# natb_square_chip.net
KiCad netlist of a schematic drawn in EAGLE
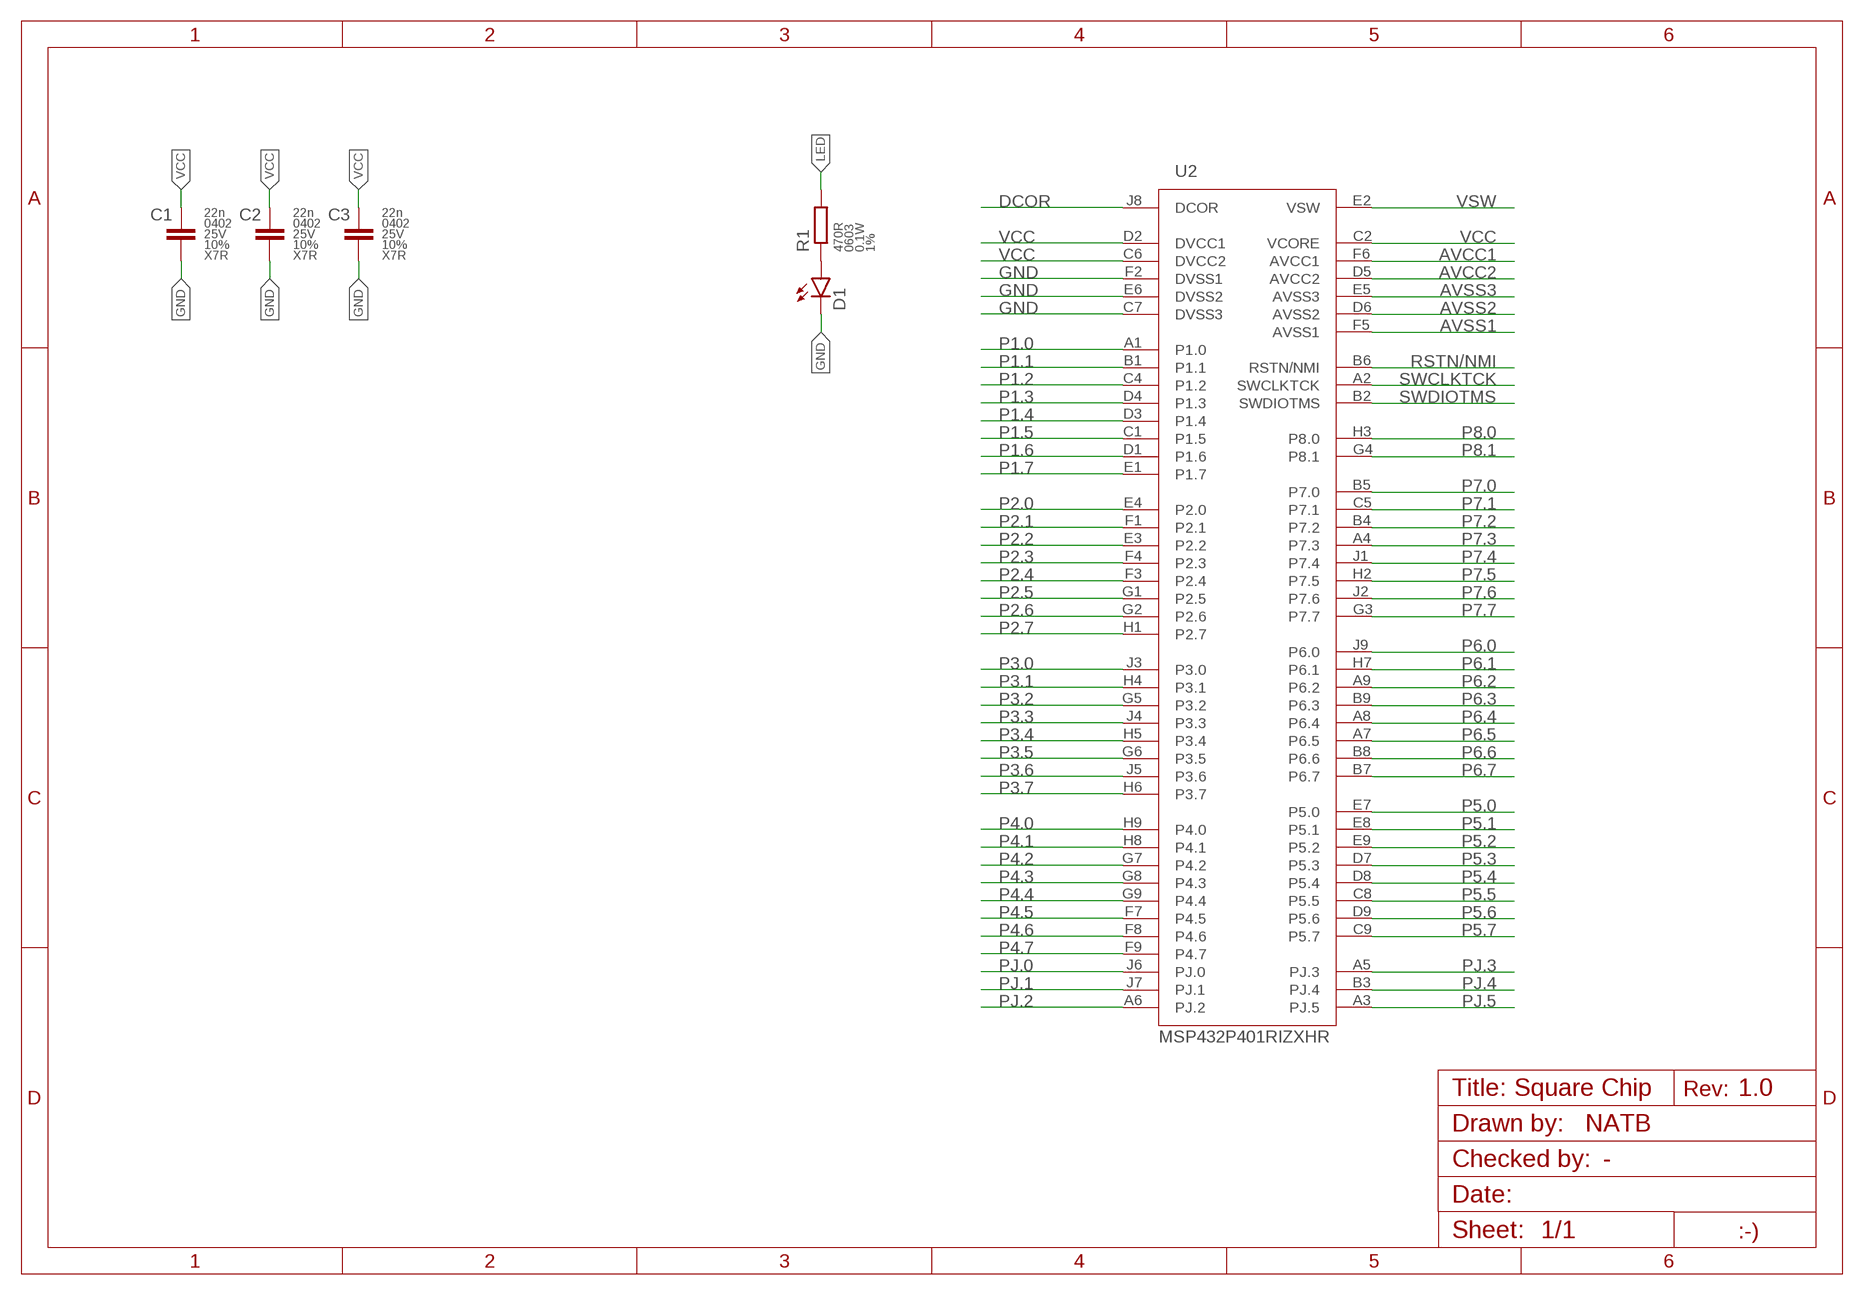
[diagram p0: schematic, sheet 1]

(export (version "E")
  (design (tool "Eeschema 10.0.6"))
  (components
    (comp (ref "C1")
      (value "22n")
      (footprint "eagle-import:C0402")
      (fields
        (field (name "PACKAGE-IN") "0402")
        (field (name "VOLTAGE") "25V")
        (field (name "TOLERANCE") "10%")
        (field (name "DIELECTRIC") "X7R")
        (field (name "MF") "Wurth Electronics")
        (field (name "MPN") "885012205052")
      )
      (libsource (lib "eagle-import") (part "22NF-0402-25V-10%"))
    )
    (comp (ref "C2")
      (value "22n")
      (footprint "eagle-import:C0402")
      (fields
        (field (name "PACKAGE-IN") "0402")
        (field (name "VOLTAGE") "25V")
        (field (name "TOLERANCE") "10%")
        (field (name "DIELECTRIC") "X7R")
        (field (name "MF") "Wurth Electronics")
        (field (name "MPN") "885012205052")
      )
      (libsource (lib "eagle-import") (part "22NF-0402-25V-10%"))
    )
    (comp (ref "C3")
      (value "22n")
      (footprint "eagle-import:C0402")
      (fields
        (field (name "PACKAGE-IN") "0402")
        (field (name "VOLTAGE") "25V")
        (field (name "TOLERANCE") "10%")
        (field (name "DIELECTRIC") "X7R")
        (field (name "MF") "Wurth Electronics")
        (field (name "MPN") "885012205052")
      )
      (libsource (lib "eagle-import") (part "22NF-0402-25V-10%"))
    )
    (comp (ref "D1")
      (value "LEDCHIP-LED0603")
      (footprint "eagle-import:CHIP-LED0603")
      (libsource (lib "eagle-import") (part "LEDCHIP-LED0603"))
    )
    (comp (ref "R1")
      (value "470R")
      (footprint "eagle-import:R0603")
      (fields
        (field (name "PACKAGE-IN") "0603")
        (field (name "POWER") "0.1W")
        (field (name "TOLERANCE") "1%")
        (field (name "MF") "Yageo")
        (field (name "MPN") "RC0603FR-07470RL")
        (field (name "VOLTAGE") "75V")
      )
      (libsource (lib "eagle-import") (part "470OHM-0603-1/10W-1%"))
    )
    (comp (ref "U2")
      (value "MSP432P401RIZXHR")
      (footprint "eagle-import:BGA80")
      (fields
        (field (name "DIGIKEY_PARTNO") "296-45566-6-ND")
        (field (name "MANUFACTURER") "Texas Instruments")
        (field (name "CREATED_BY") "PCBLayout.com")
      )
      (libsource (lib "eagle-import") (part "MSP432P401RIZXHR"))
    )
  )
  (nets
    (net (code "1") (name "/AVCC1") (class "Default")
      (node (ref "U2") (pin "F6") (pinfunction "AVCC1_F6") (pintype "power_in"))
    )
    (net (code "2") (name "/AVCC2") (class "Default")
      (node (ref "U2") (pin "D5") (pinfunction "AVCC2_D5") (pintype "power_in"))
    )
    (net (code "3") (name "/AVSS1") (class "Default")
      (node (ref "U2") (pin "F5") (pinfunction "AVSS1_F5") (pintype "power_in"))
    )
    (net (code "4") (name "/AVSS2") (class "Default")
      (node (ref "U2") (pin "D6") (pinfunction "AVSS2_D6") (pintype "power_in"))
    )
    (net (code "5") (name "/AVSS3") (class "Default")
      (node (ref "U2") (pin "E5") (pinfunction "AVSS3_E5") (pintype "power_in"))
    )
    (net (code "6") (name "/DCOR") (class "Default")
      (node (ref "U2") (pin "J8") (pinfunction "DCOR_J8") (pintype "power_in"))
    )
    (net (code "7") (name "/P1.0") (class "Default")
      (node (ref "U2") (pin "A1") (pinfunction "P1.0_A1") (pintype "bidirectional"))
    )
    (net (code "8") (name "/P1.1") (class "Default")
      (node (ref "U2") (pin "B1") (pinfunction "P1.1_B1") (pintype "bidirectional"))
    )
    (net (code "9") (name "/P1.2") (class "Default")
      (node (ref "U2") (pin "C4") (pinfunction "P1.2_C4") (pintype "bidirectional"))
    )
    (net (code "10") (name "/P1.3") (class "Default")
      (node (ref "U2") (pin "D4") (pinfunction "P1.3_D4") (pintype "bidirectional"))
    )
    (net (code "11") (name "/P1.4") (class "Default")
      (node (ref "U2") (pin "D3") (pinfunction "P1.4_D3") (pintype "bidirectional"))
    )
    (net (code "12") (name "/P1.5") (class "Default")
      (node (ref "U2") (pin "C1") (pinfunction "P1.5_C1") (pintype "bidirectional"))
    )
    (net (code "13") (name "/P1.6") (class "Default")
      (node (ref "U2") (pin "D1") (pinfunction "P1.6_D1") (pintype "bidirectional"))
    )
    (net (code "14") (name "/P1.7") (class "Default")
      (node (ref "U2") (pin "E1") (pinfunction "P1.7_E1") (pintype "bidirectional"))
    )
    (net (code "15") (name "/P2.0") (class "Default")
      (node (ref "U2") (pin "E4") (pinfunction "P2.0_E4") (pintype "bidirectional"))
    )
    (net (code "16") (name "/P2.1") (class "Default")
      (node (ref "U2") (pin "F1") (pinfunction "P2.1_F1") (pintype "bidirectional"))
    )
    (net (code "17") (name "/P2.2") (class "Default")
      (node (ref "U2") (pin "E3") (pinfunction "P2.2_E3") (pintype "bidirectional"))
    )
    (net (code "18") (name "/P2.3") (class "Default")
      (node (ref "U2") (pin "F4") (pinfunction "P2.3_F4") (pintype "bidirectional"))
    )
    (net (code "19") (name "/P2.4") (class "Default")
      (node (ref "U2") (pin "F3") (pinfunction "P2.4_F3") (pintype "bidirectional"))
    )
    (net (code "20") (name "/P2.5") (class "Default")
      (node (ref "U2") (pin "G1") (pinfunction "P2.5_G1") (pintype "bidirectional"))
    )
    (net (code "21") (name "/P2.6") (class "Default")
      (node (ref "U2") (pin "G2") (pinfunction "P2.6_G2") (pintype "bidirectional"))
    )
    (net (code "22") (name "/P2.7") (class "Default")
      (node (ref "U2") (pin "H1") (pinfunction "P2.7_H1") (pintype "bidirectional"))
    )
    (net (code "23") (name "/P3.0") (class "Default")
      (node (ref "U2") (pin "J3") (pinfunction "P3.0_J3") (pintype "bidirectional"))
    )
    (net (code "24") (name "/P3.1") (class "Default")
      (node (ref "U2") (pin "H4") (pinfunction "P3.1_H4") (pintype "bidirectional"))
    )
    (net (code "25") (name "/P3.2") (class "Default")
      (node (ref "U2") (pin "G5") (pinfunction "P3.2_G5") (pintype "bidirectional"))
    )
    (net (code "26") (name "/P3.3") (class "Default")
      (node (ref "U2") (pin "J4") (pinfunction "P3.3_J4") (pintype "bidirectional"))
    )
    (net (code "27") (name "/P3.4") (class "Default")
      (node (ref "U2") (pin "H5") (pinfunction "P3.4_H5") (pintype "bidirectional"))
    )
    (net (code "28") (name "/P3.5") (class "Default")
      (node (ref "U2") (pin "G6") (pinfunction "P3.5_G6") (pintype "bidirectional"))
    )
    (net (code "29") (name "/P3.6") (class "Default")
      (node (ref "U2") (pin "J5") (pinfunction "P3.6_J5") (pintype "bidirectional"))
    )
    (net (code "30") (name "/P3.7") (class "Default")
      (node (ref "U2") (pin "H6") (pinfunction "P3.7_H6") (pintype "bidirectional"))
    )
    (net (code "31") (name "/P4.0") (class "Default")
      (node (ref "U2") (pin "H9") (pinfunction "P4.0_H9") (pintype "bidirectional"))
    )
    (net (code "32") (name "/P4.1") (class "Default")
      (node (ref "U2") (pin "H8") (pinfunction "P4.1_H8") (pintype "bidirectional"))
    )
    (net (code "33") (name "/P4.2") (class "Default")
      (node (ref "U2") (pin "G7") (pinfunction "P4.2_G7") (pintype "bidirectional"))
    )
    (net (code "34") (name "/P4.3") (class "Default")
      (node (ref "U2") (pin "G8") (pinfunction "P4.3_G8") (pintype "bidirectional"))
    )
    (net (code "35") (name "/P4.4") (class "Default")
      (node (ref "U2") (pin "G9") (pinfunction "P4.4_G9") (pintype "bidirectional"))
    )
    (net (code "36") (name "/P4.5") (class "Default")
      (node (ref "U2") (pin "F7") (pinfunction "P4.5_F7") (pintype "bidirectional"))
    )
    (net (code "37") (name "/P4.6") (class "Default")
      (node (ref "U2") (pin "F8") (pinfunction "P4.6_F8") (pintype "bidirectional"))
    )
    (net (code "38") (name "/P4.7") (class "Default")
      (node (ref "U2") (pin "F9") (pinfunction "P4.7_F9") (pintype "bidirectional"))
    )
    (net (code "39") (name "/P5.0") (class "Default")
      (node (ref "U2") (pin "E7") (pinfunction "P5.0_E7") (pintype "bidirectional"))
    )
    (net (code "40") (name "/P5.1") (class "Default")
      (node (ref "U2") (pin "E8") (pinfunction "P5.1_E8") (pintype "bidirectional"))
    )
    (net (code "41") (name "/P5.2") (class "Default")
      (node (ref "U2") (pin "E9") (pinfunction "P5.2_E9") (pintype "bidirectional"))
    )
    (net (code "42") (name "/P5.3") (class "Default")
      (node (ref "U2") (pin "D7") (pinfunction "P5.3_D7") (pintype "bidirectional"))
    )
    (net (code "43") (name "/P5.4") (class "Default")
      (node (ref "U2") (pin "D8") (pinfunction "P5.4_D8") (pintype "bidirectional"))
    )
    (net (code "44") (name "/P5.5") (class "Default")
      (node (ref "U2") (pin "C8") (pinfunction "P5.5_C8") (pintype "bidirectional"))
    )
    (net (code "45") (name "/P5.6") (class "Default")
      (node (ref "U2") (pin "D9") (pinfunction "P5.6_D9") (pintype "bidirectional"))
    )
    (net (code "46") (name "/P5.7") (class "Default")
      (node (ref "U2") (pin "C9") (pinfunction "P5.7_C9") (pintype "bidirectional"))
    )
    (net (code "47") (name "/P6.0") (class "Default")
      (node (ref "U2") (pin "J9") (pinfunction "P6.0_J9") (pintype "bidirectional"))
    )
    (net (code "48") (name "/P6.1") (class "Default")
      (node (ref "U2") (pin "H7") (pinfunction "P6.1_H7") (pintype "bidirectional"))
    )
    (net (code "49") (name "/P6.2") (class "Default")
      (node (ref "U2") (pin "A9") (pinfunction "P6.2_A9") (pintype "bidirectional"))
    )
    (net (code "50") (name "/P6.3") (class "Default")
      (node (ref "U2") (pin "B9") (pinfunction "P6.3_B9") (pintype "bidirectional"))
    )
    (net (code "51") (name "/P6.4") (class "Default")
      (node (ref "U2") (pin "A8") (pinfunction "P6.4_A8") (pintype "bidirectional"))
    )
    (net (code "52") (name "/P6.5") (class "Default")
      (node (ref "U2") (pin "A7") (pinfunction "P6.5_A7") (pintype "bidirectional"))
    )
    (net (code "53") (name "/P6.6") (class "Default")
      (node (ref "U2") (pin "B8") (pinfunction "P6.6_B8") (pintype "bidirectional"))
    )
    (net (code "54") (name "/P6.7") (class "Default")
      (node (ref "U2") (pin "B7") (pinfunction "P6.7_B7") (pintype "bidirectional"))
    )
    (net (code "55") (name "/P7.0") (class "Default")
      (node (ref "U2") (pin "B5") (pinfunction "P7.0_B5") (pintype "bidirectional"))
    )
    (net (code "56") (name "/P7.1") (class "Default")
      (node (ref "U2") (pin "C5") (pinfunction "P7.1_C5") (pintype "bidirectional"))
    )
    (net (code "57") (name "/P7.2") (class "Default")
      (node (ref "U2") (pin "B4") (pinfunction "P7.2_B4") (pintype "bidirectional"))
    )
    (net (code "58") (name "/P7.3") (class "Default")
      (node (ref "U2") (pin "A4") (pinfunction "P7.3_A4") (pintype "bidirectional"))
    )
    (net (code "59") (name "/P7.4") (class "Default")
      (node (ref "U2") (pin "J1") (pinfunction "P7.4_J1") (pintype "bidirectional"))
    )
    (net (code "60") (name "/P7.5") (class "Default")
      (node (ref "U2") (pin "H2") (pinfunction "P7.5_H2") (pintype "bidirectional"))
    )
    (net (code "61") (name "/P7.6") (class "Default")
      (node (ref "U2") (pin "J2") (pinfunction "P7.6_J2") (pintype "bidirectional"))
    )
    (net (code "62") (name "/P7.7") (class "Default")
      (node (ref "U2") (pin "G3") (pinfunction "P7.7_G3") (pintype "bidirectional"))
    )
    (net (code "63") (name "/P8.0") (class "Default")
      (node (ref "U2") (pin "H3") (pinfunction "P8.0_H3") (pintype "bidirectional"))
    )
    (net (code "64") (name "/P8.1") (class "Default")
      (node (ref "U2") (pin "G4") (pinfunction "P8.1_G4") (pintype "bidirectional"))
    )
    (net (code "65") (name "/PJ.0") (class "Default")
      (node (ref "U2") (pin "J6") (pinfunction "PJ.0_J6") (pintype "bidirectional"))
    )
    (net (code "66") (name "/PJ.1") (class "Default")
      (node (ref "U2") (pin "J7") (pinfunction "PJ.1_J7") (pintype "bidirectional"))
    )
    (net (code "67") (name "/PJ.2") (class "Default")
      (node (ref "U2") (pin "A6") (pinfunction "PJ.2_A6") (pintype "bidirectional"))
    )
    (net (code "68") (name "/PJ.3") (class "Default")
      (node (ref "U2") (pin "A5") (pinfunction "PJ.3_A5") (pintype "bidirectional"))
    )
    (net (code "69") (name "/PJ.4") (class "Default")
      (node (ref "U2") (pin "B3") (pinfunction "PJ.4_B3") (pintype "bidirectional"))
    )
    (net (code "70") (name "/PJ.5") (class "Default")
      (node (ref "U2") (pin "A3") (pinfunction "PJ.5_A3") (pintype "bidirectional"))
    )
    (net (code "71") (name "/RSTN{slash}NMI") (class "Default")
      (node (ref "U2") (pin "B6") (pinfunction "RSTN/NMI_B6") (pintype "bidirectional"))
    )
    (net (code "72") (name "/SWCLKTCK") (class "Default")
      (node (ref "U2") (pin "A2") (pinfunction "SWCLKTCK_A2") (pintype "bidirectional"))
    )
    (net (code "73") (name "/SWDIOTMS") (class "Default")
      (node (ref "U2") (pin "B2") (pinfunction "SWDIOTMS_B2") (pintype "bidirectional"))
    )
    (net (code "74") (name "/VSW") (class "Default")
      (node (ref "U2") (pin "E2") (pinfunction "VSW_E2") (pintype "power_in"))
    )
    (net (code "75") (name "GND") (class "Default")
      (node (ref "C1") (pin "2") (pinfunction "2_2") (pintype "passive"))
      (node (ref "C2") (pin "2") (pinfunction "2_2") (pintype "passive"))
      (node (ref "C3") (pin "2") (pinfunction "2_2") (pintype "passive"))
      (node (ref "D1") (pin "C") (pinfunction "C_C") (pintype "passive"))
      (node (ref "U2") (pin "C7") (pinfunction "DVSS3_C7") (pintype "power_in"))
      (node (ref "U2") (pin "E6") (pinfunction "DVSS2_E6") (pintype "power_in"))
      (node (ref "U2") (pin "F2") (pinfunction "DVSS1_F2") (pintype "power_in"))
    )
    (net (code "76") (name "LED") (class "Default")
      (node (ref "R1") (pin "2") (pinfunction "2_2") (pintype "passive"))
    )
    (net (code "77") (name "Net-(D1-PadA)") (class "Default")
      (node (ref "D1") (pin "A") (pinfunction "A_A") (pintype "passive"))
      (node (ref "R1") (pin "1") (pinfunction "1_1") (pintype "passive"))
    )
    (net (code "78") (name "VCC") (class "Default")
      (node (ref "C1") (pin "1") (pinfunction "1_1") (pintype "passive"))
      (node (ref "C2") (pin "1") (pinfunction "1_1") (pintype "passive"))
      (node (ref "C3") (pin "1") (pinfunction "1_1") (pintype "passive"))
      (node (ref "U2") (pin "C2") (pinfunction "VCORE_C2") (pintype "power_in"))
      (node (ref "U2") (pin "C6") (pinfunction "DVCC2_C6") (pintype "power_in"))
      (node (ref "U2") (pin "D2") (pinfunction "DVCC1_D2") (pintype "power_in"))
    )
  )
)
